# PCB-ENCODER4N.net
KiCad netlist of a schematic drawn in EAGLE
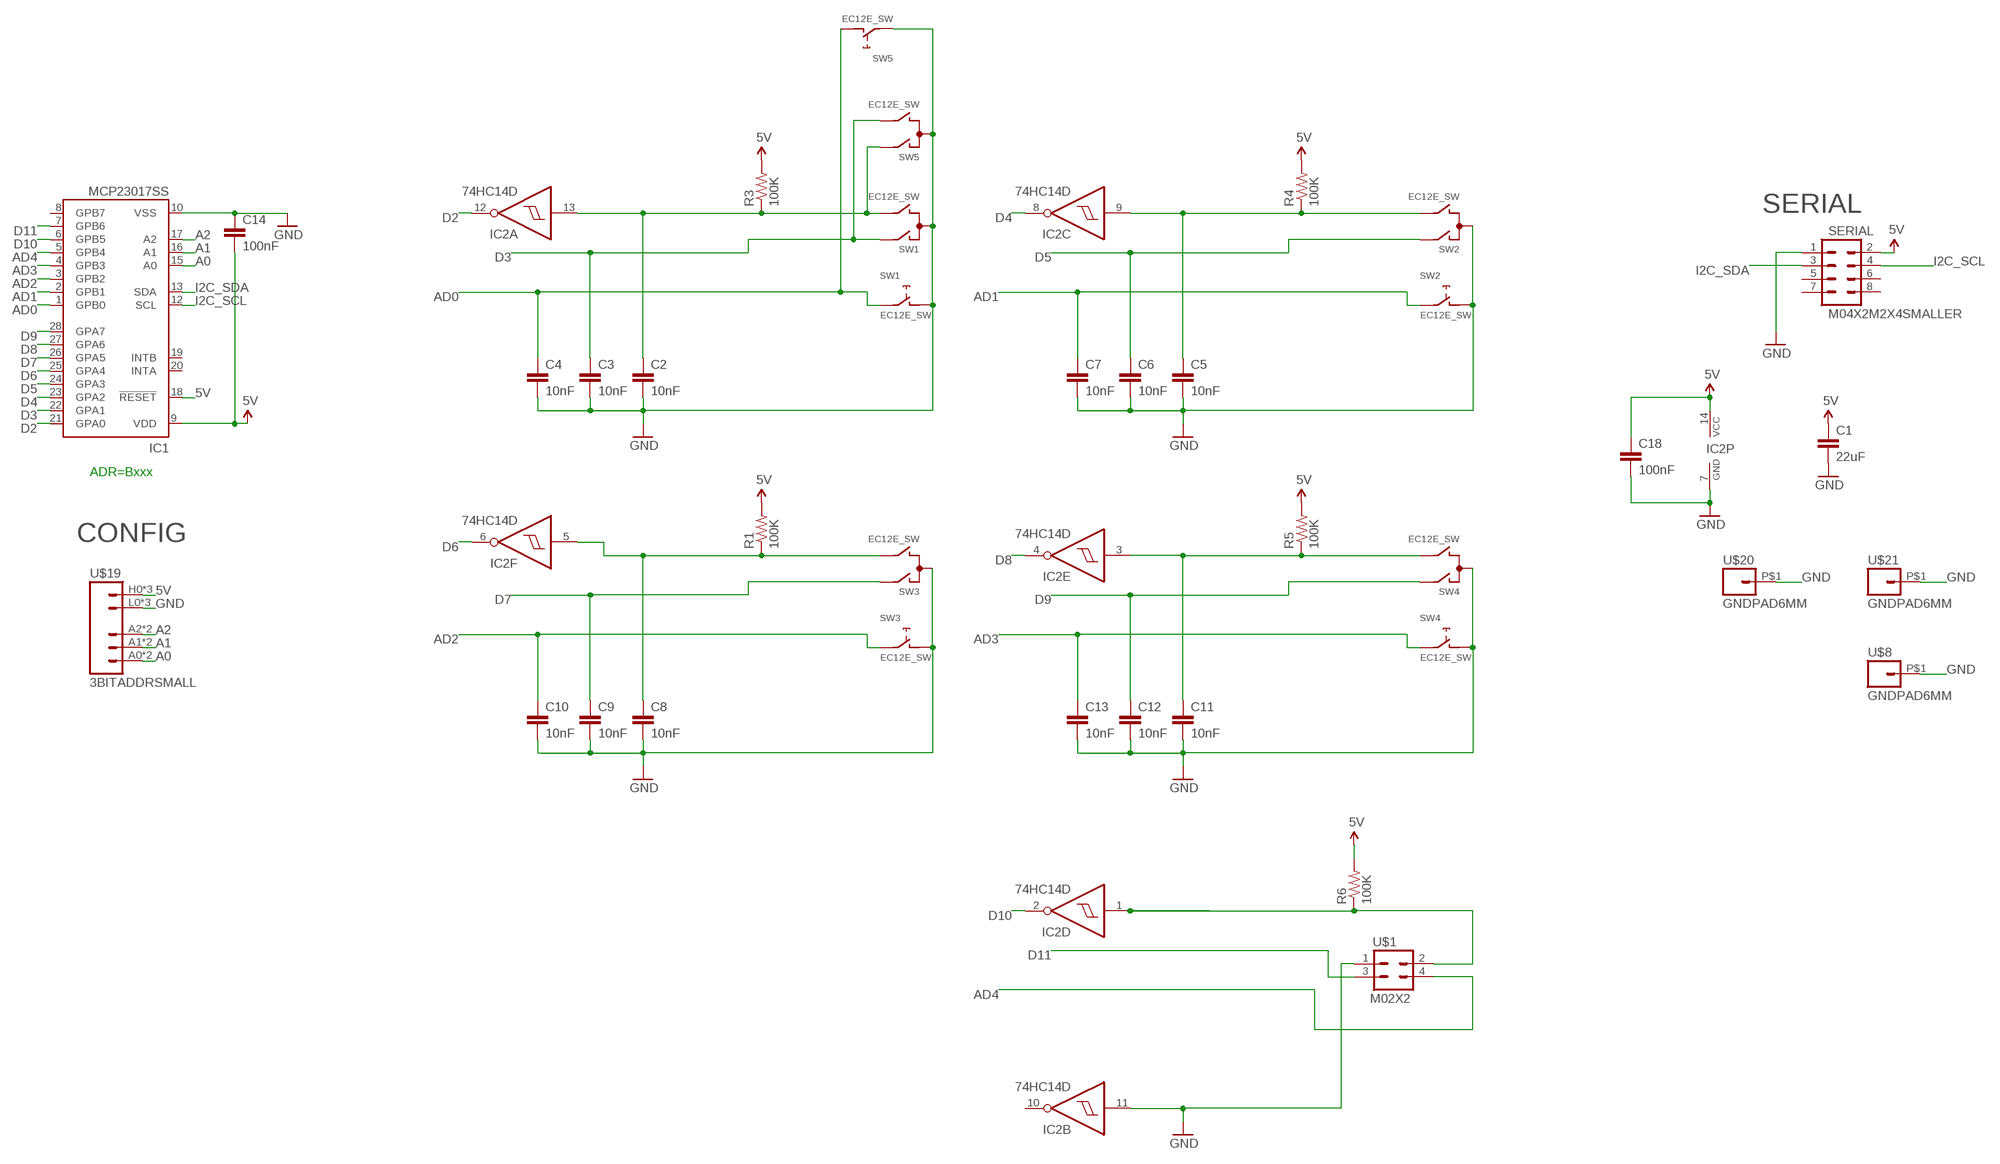
[diagram p0: schematic, sheet 1]

(export (version "E")
  (design (tool "Eeschema 10.0.6"))
  (components
    (comp (ref "C1")
      (value "22uF")
      (footprint "eagle-import:0805")
      (libsource (lib "eagle-import") (part "CAP0805"))
    )
    (comp (ref "C2")
      (value "10nF")
      (footprint "eagle-import:0603-CAP")
      (libsource (lib "eagle-import") (part "CAP0603-CAP"))
    )
    (comp (ref "C3")
      (value "10nF")
      (footprint "eagle-import:0603-CAP")
      (libsource (lib "eagle-import") (part "CAP0603-CAP"))
    )
    (comp (ref "C4")
      (value "10nF")
      (footprint "eagle-import:0603-CAP")
      (libsource (lib "eagle-import") (part "CAP0603-CAP"))
    )
    (comp (ref "C5")
      (value "10nF")
      (footprint "eagle-import:0603-CAP")
      (libsource (lib "eagle-import") (part "CAP0603-CAP"))
    )
    (comp (ref "C6")
      (value "10nF")
      (footprint "eagle-import:0603-CAP")
      (libsource (lib "eagle-import") (part "CAP0603-CAP"))
    )
    (comp (ref "C7")
      (value "10nF")
      (footprint "eagle-import:0603-CAP")
      (libsource (lib "eagle-import") (part "CAP0603-CAP"))
    )
    (comp (ref "C8")
      (value "10nF")
      (footprint "eagle-import:0603-CAP")
      (libsource (lib "eagle-import") (part "CAP0603-CAP"))
    )
    (comp (ref "C9")
      (value "10nF")
      (footprint "eagle-import:0603-CAP")
      (libsource (lib "eagle-import") (part "CAP0603-CAP"))
    )
    (comp (ref "C10")
      (value "10nF")
      (footprint "eagle-import:0603-CAP")
      (libsource (lib "eagle-import") (part "CAP0603-CAP"))
    )
    (comp (ref "C11")
      (value "10nF")
      (footprint "eagle-import:0603-CAP")
      (libsource (lib "eagle-import") (part "CAP0603-CAP"))
    )
    (comp (ref "C12")
      (value "10nF")
      (footprint "eagle-import:0603-CAP")
      (libsource (lib "eagle-import") (part "CAP0603-CAP"))
    )
    (comp (ref "C13")
      (value "10nF")
      (footprint "eagle-import:0603-CAP")
      (libsource (lib "eagle-import") (part "CAP0603-CAP"))
    )
    (comp (ref "C14")
      (value "100nF")
      (footprint "eagle-import:0603-CAP")
      (libsource (lib "eagle-import") (part "CAP0603-CAP"))
    )
    (comp (ref "C18")
      (value "100nF")
      (footprint "eagle-import:0603-CAP")
      (libsource (lib "eagle-import") (part "CAP0603-CAP"))
    )
    (comp (ref "IC1")
      (value "MCP23017SS")
      (footprint "eagle-import:SSOP28")
      (fields
        (field (name "MF") "MICROCHIP")
        (field (name "MPN") "MCP23017-E/SS")
        (field (name "MPN_1") "MCP23017-E/SS")
        (field (name "OC_FARNELL") "1467674")
        (field (name "OC_NEWARK") "31K2960")
      )
      (libsource (lib "eagle-import") (part "MCP23017SS"))
    )
    (comp (ref "IC2")
      (value "74HC14D")
      (footprint "eagle-import:SO14")
      (libsource (lib "eagle-import") (part "7414DHC"))
    )
    (comp (ref "R1")
      (value "100K")
      (footprint "eagle-import:0603-RES")
      (libsource (lib "eagle-import") (part "RESISTOR0603-RES"))
    )
    (comp (ref "R3")
      (value "100K")
      (footprint "eagle-import:0603-RES")
      (libsource (lib "eagle-import") (part "RESISTOR0603-RES"))
    )
    (comp (ref "R4")
      (value "100K")
      (footprint "eagle-import:0603-RES")
      (libsource (lib "eagle-import") (part "RESISTOR0603-RES"))
    )
    (comp (ref "R5")
      (value "100K")
      (footprint "eagle-import:0603-RES")
      (libsource (lib "eagle-import") (part "RESISTOR0603-RES"))
    )
    (comp (ref "R6")
      (value "100K")
      (footprint "eagle-import:0603-RES")
      (libsource (lib "eagle-import") (part "RESISTOR0603-RES"))
    )
    (comp (ref "SERIAL")
      (value "M04X2M2X4SMALLER")
      (footprint "eagle-import:M2X4SMALLER")
      (libsource (lib "eagle-import") (part "M04X2M2X4SMALLER"))
    )
    (comp (ref "SW1")
      (value "EC12E_SW")
      (footprint "eagle-import:ALPS_EC12E_SW")
      (fields (field (name "MPN") "EC12E2424407"))
      (libsource (lib "eagle-import") (part "EC12E_SW"))
    )
    (comp (ref "SW2")
      (value "EC12E_SW")
      (footprint "eagle-import:ALPS_EC12E_SW")
      (fields (field (name "MPN") "EC12E2424407"))
      (libsource (lib "eagle-import") (part "EC12E_SW"))
    )
    (comp (ref "SW3")
      (value "EC12E_SW")
      (footprint "eagle-import:ALPS_EC12E_SW")
      (fields (field (name "MPN") "EC12E2424407"))
      (libsource (lib "eagle-import") (part "EC12E_SW"))
    )
    (comp (ref "SW4")
      (value "EC12E_SW")
      (footprint "eagle-import:ALPS_EC12E_SW")
      (fields (field (name "MPN") "EC12E2424407"))
      (libsource (lib "eagle-import") (part "EC12E_SW"))
    )
    (comp (ref "SW5")
      (value "EC12E_SW")
      (footprint "eagle-import:ALPS_EC12E_SW")
      (fields (field (name "MPN") "EC12E2424407"))
      (libsource (lib "eagle-import") (part "EC12E_SW"))
    )
    (comp (ref "U$1")
      (value "M02X2")
      (footprint "eagle-import:2X2")
      (libsource (lib "eagle-import") (part "M02X2"))
    )
    (comp (ref "U$8")
      (value "GNDPAD6MM")
      (footprint "eagle-import:3.2MMPAD6MM")
      (libsource (lib "eagle-import") (part "GNDPAD6MM"))
    )
    (comp (ref "U$19")
      (value "3BITADDRSMALL")
      (footprint "eagle-import:3BITADDR_SMALL")
      (libsource (lib "eagle-import") (part "3BITADDRSMALL"))
    )
    (comp (ref "U$20")
      (value "GNDPAD6MM")
      (footprint "eagle-import:3.2MMPAD6MM")
      (libsource (lib "eagle-import") (part "GNDPAD6MM"))
    )
    (comp (ref "U$21")
      (value "GNDPAD6MM")
      (footprint "eagle-import:3.2MMPAD6MM")
      (libsource (lib "eagle-import") (part "GNDPAD6MM"))
    )
  )
  (nets
    (net (code "1") (name "/A0") (class "Default")
      (node (ref "IC1") (pin "15") (pinfunction "A0_15") (pintype "input"))
      (node (ref "U$19") (pin "A0") (pinfunction "A0_A0") (pintype "passive"))
      (node (ref "U$19") (pin "AS0") (pinfunction "A0_AS0") (pintype "passive"))
    )
    (net (code "2") (name "/A1") (class "Default")
      (node (ref "IC1") (pin "16") (pinfunction "A1_16") (pintype "input"))
      (node (ref "U$19") (pin "A1") (pinfunction "A1_A1") (pintype "passive"))
      (node (ref "U$19") (pin "AS1") (pinfunction "A1_AS1") (pintype "passive"))
    )
    (net (code "3") (name "/A2") (class "Default")
      (node (ref "IC1") (pin "17") (pinfunction "A2_17") (pintype "input"))
      (node (ref "U$19") (pin "A2") (pinfunction "A2_A2") (pintype "passive"))
      (node (ref "U$19") (pin "AS2") (pinfunction "A2_AS2") (pintype "passive"))
    )
    (net (code "4") (name "/AD0") (class "Default")
      (node (ref "C4") (pin "1") (pinfunction "1_1") (pintype "passive"))
      (node (ref "IC1") (pin "1") (pinfunction "GPB0_1") (pintype "bidirectional"))
      (node (ref "SW1") (pin "E") (pinfunction "2_E") (pintype "passive"))
      (node (ref "SW5") (pin "D") (pinfunction "1_D") (pintype "passive"))
    )
    (net (code "5") (name "/AD1") (class "Default")
      (node (ref "C7") (pin "1") (pinfunction "1_1") (pintype "passive"))
      (node (ref "IC1") (pin "2") (pinfunction "GPB1_2") (pintype "bidirectional"))
      (node (ref "SW2") (pin "E") (pinfunction "2_E") (pintype "passive"))
    )
    (net (code "6") (name "/AD2") (class "Default")
      (node (ref "C10") (pin "1") (pinfunction "1_1") (pintype "passive"))
      (node (ref "IC1") (pin "3") (pinfunction "GPB2_3") (pintype "bidirectional"))
      (node (ref "SW3") (pin "E") (pinfunction "2_E") (pintype "passive"))
    )
    (net (code "7") (name "/AD3") (class "Default")
      (node (ref "C13") (pin "1") (pinfunction "1_1") (pintype "passive"))
      (node (ref "IC1") (pin "4") (pinfunction "GPB3_4") (pintype "bidirectional"))
      (node (ref "SW4") (pin "E") (pinfunction "2_E") (pintype "passive"))
    )
    (net (code "8") (name "/AD4") (class "Default")
      (node (ref "IC1") (pin "5") (pinfunction "GPB4_5") (pintype "bidirectional"))
      (node (ref "U$1") (pin "4") (pinfunction "4_4") (pintype "passive"))
    )
    (net (code "9") (name "/D2") (class "Default")
      (node (ref "IC1") (pin "21") (pinfunction "GPA0_21") (pintype "bidirectional"))
      (node (ref "IC2") (pin "12") (pinfunction "O_12") (pintype "output"))
    )
    (net (code "10") (name "/D3") (class "Default")
      (node (ref "C3") (pin "1") (pinfunction "1_1") (pintype "passive"))
      (node (ref "IC1") (pin "22") (pinfunction "GPA1_22") (pintype "bidirectional"))
      (node (ref "SW1") (pin "A") (pinfunction "A_A") (pintype "passive"))
      (node (ref "SW5") (pin "B") (pinfunction "B_B") (pintype "passive"))
    )
    (net (code "11") (name "/D4") (class "Default")
      (node (ref "IC1") (pin "23") (pinfunction "GPA2_23") (pintype "bidirectional"))
      (node (ref "IC2") (pin "8") (pinfunction "O_8") (pintype "output"))
    )
    (net (code "12") (name "/D5") (class "Default")
      (node (ref "C6") (pin "1") (pinfunction "1_1") (pintype "passive"))
      (node (ref "IC1") (pin "24") (pinfunction "GPA3_24") (pintype "bidirectional"))
      (node (ref "SW2") (pin "A") (pinfunction "A_A") (pintype "passive"))
    )
    (net (code "13") (name "/D6") (class "Default")
      (node (ref "IC1") (pin "25") (pinfunction "GPA4_25") (pintype "bidirectional"))
      (node (ref "IC2") (pin "6") (pinfunction "O_6") (pintype "output"))
    )
    (net (code "14") (name "/D7") (class "Default")
      (node (ref "C9") (pin "1") (pinfunction "1_1") (pintype "passive"))
      (node (ref "IC1") (pin "26") (pinfunction "GPA5_26") (pintype "bidirectional"))
      (node (ref "SW3") (pin "A") (pinfunction "A_A") (pintype "passive"))
    )
    (net (code "15") (name "/D8") (class "Default")
      (node (ref "IC1") (pin "27") (pinfunction "GPA6_27") (pintype "bidirectional"))
      (node (ref "IC2") (pin "4") (pinfunction "O_4") (pintype "output"))
    )
    (net (code "16") (name "/D9") (class "Default")
      (node (ref "C12") (pin "1") (pinfunction "1_1") (pintype "passive"))
      (node (ref "IC1") (pin "28") (pinfunction "GPA7_28") (pintype "bidirectional"))
      (node (ref "SW4") (pin "A") (pinfunction "A_A") (pintype "passive"))
    )
    (net (code "17") (name "/D10") (class "Default")
      (node (ref "IC1") (pin "6") (pinfunction "GPB5_6") (pintype "bidirectional"))
      (node (ref "IC2") (pin "2") (pinfunction "O_2") (pintype "output"))
    )
    (net (code "18") (name "/D11") (class "Default")
      (node (ref "IC1") (pin "7") (pinfunction "GPB6_7") (pintype "bidirectional"))
      (node (ref "U$1") (pin "3") (pinfunction "3_3") (pintype "passive"))
    )
    (net (code "19") (name "/I2C_SCL") (class "Default")
      (node (ref "IC1") (pin "12") (pinfunction "SCL_12") (pintype "input"))
      (node (ref "SERIAL") (pin "4") (pinfunction "4_4") (pintype "passive"))
    )
    (net (code "20") (name "/I2C_SDA") (class "Default")
      (node (ref "IC1") (pin "13") (pinfunction "SDA_13") (pintype "bidirectional"))
      (node (ref "SERIAL") (pin "3") (pinfunction "3_3") (pintype "passive"))
    )
    (net (code "21") (name "5V") (class "Default")
      (node (ref "C1") (pin "1") (pinfunction "1_1") (pintype "passive"))
      (node (ref "C14") (pin "2") (pinfunction "2_2") (pintype "passive"))
      (node (ref "C18") (pin "1") (pinfunction "1_1") (pintype "passive"))
      (node (ref "IC1") (pin "18") (pinfunction "~{RESET}_18") (pintype "input"))
      (node (ref "IC1") (pin "9") (pinfunction "VDD_9") (pintype "power_in"))
      (node (ref "IC2") (pin "14") (pinfunction "VCC_14") (pintype "power_in"))
      (node (ref "R1") (pin "2") (pinfunction "2_2") (pintype "passive"))
      (node (ref "R3") (pin "2") (pinfunction "2_2") (pintype "passive"))
      (node (ref "R4") (pin "2") (pinfunction "2_2") (pintype "passive"))
      (node (ref "R5") (pin "2") (pinfunction "2_2") (pintype "passive"))
      (node (ref "R6") (pin "2") (pinfunction "2_2") (pintype "passive"))
      (node (ref "SERIAL") (pin "2") (pinfunction "2_2") (pintype "passive"))
      (node (ref "U$19") (pin "H0") (pinfunction "VCC_H0") (pintype "passive"))
      (node (ref "U$19") (pin "H1") (pinfunction "VCC_H1") (pintype "passive"))
      (node (ref "U$19") (pin "H2") (pinfunction "VCC_H2") (pintype "passive"))
    )
    (net (code "22") (name "GND") (class "Default")
      (node (ref "C1") (pin "2") (pinfunction "2_2") (pintype "passive"))
      (node (ref "C10") (pin "2") (pinfunction "2_2") (pintype "passive"))
      (node (ref "C11") (pin "2") (pinfunction "2_2") (pintype "passive"))
      (node (ref "C12") (pin "2") (pinfunction "2_2") (pintype "passive"))
      (node (ref "C13") (pin "2") (pinfunction "2_2") (pintype "passive"))
      (node (ref "C14") (pin "1") (pinfunction "1_1") (pintype "passive"))
      (node (ref "C18") (pin "2") (pinfunction "2_2") (pintype "passive"))
      (node (ref "C2") (pin "2") (pinfunction "2_2") (pintype "passive"))
      (node (ref "C3") (pin "2") (pinfunction "2_2") (pintype "passive"))
      (node (ref "C4") (pin "2") (pinfunction "2_2") (pintype "passive"))
      (node (ref "C5") (pin "2") (pinfunction "2_2") (pintype "passive"))
      (node (ref "C6") (pin "2") (pinfunction "2_2") (pintype "passive"))
      (node (ref "C7") (pin "2") (pinfunction "2_2") (pintype "passive"))
      (node (ref "C8") (pin "2") (pinfunction "2_2") (pintype "passive"))
      (node (ref "C9") (pin "2") (pinfunction "2_2") (pintype "passive"))
      (node (ref "IC1") (pin "10") (pinfunction "VSS_10") (pintype "power_in"))
      (node (ref "IC2") (pin "11") (pinfunction "I_11") (pintype "input"))
      (node (ref "IC2") (pin "7") (pinfunction "GND_7") (pintype "power_in"))
      (node (ref "SERIAL") (pin "1") (pinfunction "1_1") (pintype "passive"))
      (node (ref "SW1") (pin "C") (pinfunction "C_C") (pintype "passive"))
      (node (ref "SW1") (pin "D") (pinfunction "1_D") (pintype "passive"))
      (node (ref "SW2") (pin "C") (pinfunction "C_C") (pintype "passive"))
      (node (ref "SW2") (pin "D") (pinfunction "1_D") (pintype "passive"))
      (node (ref "SW3") (pin "C") (pinfunction "C_C") (pintype "passive"))
      (node (ref "SW3") (pin "D") (pinfunction "1_D") (pintype "passive"))
      (node (ref "SW4") (pin "C") (pinfunction "C_C") (pintype "passive"))
      (node (ref "SW4") (pin "D") (pinfunction "1_D") (pintype "passive"))
      (node (ref "SW5") (pin "C") (pinfunction "C_C") (pintype "passive"))
      (node (ref "SW5") (pin "E") (pinfunction "2_E") (pintype "passive"))
      (node (ref "U$1") (pin "1") (pinfunction "1_1") (pintype "passive"))
      (node (ref "U$19") (pin "L0") (pinfunction "GND_L0") (pintype "passive"))
      (node (ref "U$19") (pin "L1") (pinfunction "GND_L1") (pintype "passive"))
      (node (ref "U$19") (pin "L2") (pinfunction "GND_L2") (pintype "passive"))
      (node (ref "U$20") (pin "P$1") (pinfunction "1_P$1") (pintype "passive"))
      (node (ref "U$21") (pin "P$1") (pinfunction "1_P$1") (pintype "passive"))
      (node (ref "U$8") (pin "P$1") (pinfunction "1_P$1") (pintype "passive"))
    )
    (net (code "23") (name "Net-(IC2A-I)") (class "Default")
      (node (ref "C2") (pin "1") (pinfunction "1_1") (pintype "passive"))
      (node (ref "IC2") (pin "13") (pinfunction "I_13") (pintype "input"))
      (node (ref "R3") (pin "1") (pinfunction "1_1") (pintype "passive"))
      (node (ref "SW1") (pin "B") (pinfunction "B_B") (pintype "passive"))
      (node (ref "SW5") (pin "A") (pinfunction "A_A") (pintype "passive"))
    )
    (net (code "24") (name "Net-(IC2C-I)") (class "Default")
      (node (ref "C5") (pin "1") (pinfunction "1_1") (pintype "passive"))
      (node (ref "IC2") (pin "9") (pinfunction "I_9") (pintype "input"))
      (node (ref "R4") (pin "1") (pinfunction "1_1") (pintype "passive"))
      (node (ref "SW2") (pin "B") (pinfunction "B_B") (pintype "passive"))
    )
    (net (code "25") (name "Net-(IC2D-I)") (class "Default")
      (node (ref "IC2") (pin "1") (pinfunction "I_1") (pintype "input"))
      (node (ref "R6") (pin "1") (pinfunction "1_1") (pintype "passive"))
      (node (ref "U$1") (pin "2") (pinfunction "2_2") (pintype "passive"))
    )
    (net (code "26") (name "Net-(IC2E-I)") (class "Default")
      (node (ref "C11") (pin "1") (pinfunction "1_1") (pintype "passive"))
      (node (ref "IC2") (pin "3") (pinfunction "I_3") (pintype "input"))
      (node (ref "R5") (pin "1") (pinfunction "1_1") (pintype "passive"))
      (node (ref "SW4") (pin "B") (pinfunction "B_B") (pintype "passive"))
    )
    (net (code "27") (name "Net-(IC2F-I)") (class "Default")
      (node (ref "C8") (pin "1") (pinfunction "1_1") (pintype "passive"))
      (node (ref "IC2") (pin "5") (pinfunction "I_5") (pintype "input"))
      (node (ref "R1") (pin "1") (pinfunction "1_1") (pintype "passive"))
      (node (ref "SW3") (pin "B") (pinfunction "B_B") (pintype "passive"))
    )
    (net (code "28") (name "unconnected-(IC1-GPB7-Pad8)") (class "Default")
      (node (ref "IC1") (pin "8") (pinfunction "GPB7_8") (pintype "bidirectional"))
    )
    (net (code "29") (name "unconnected-(IC1-INTA-Pad20)") (class "Default")
      (node (ref "IC1") (pin "20") (pinfunction "INTA_20") (pintype "output"))
    )
    (net (code "30") (name "unconnected-(IC1-INTB-Pad19)") (class "Default")
      (node (ref "IC1") (pin "19") (pinfunction "INTB_19") (pintype "output"))
    )
    (net (code "31") (name "unconnected-(IC2B-O-Pad10)") (class "Default")
      (node (ref "IC2") (pin "10") (pinfunction "O_10") (pintype "output"))
    )
    (net (code "32") (name "unconnected-(SERIAL-Pad5)") (class "Default")
      (node (ref "SERIAL") (pin "5") (pinfunction "5_5") (pintype "passive"))
    )
    (net (code "33") (name "unconnected-(SERIAL-Pad6)") (class "Default")
      (node (ref "SERIAL") (pin "6") (pinfunction "6_6") (pintype "passive"))
    )
    (net (code "34") (name "unconnected-(SERIAL-Pad7)") (class "Default")
      (node (ref "SERIAL") (pin "7") (pinfunction "7_7") (pintype "passive"))
    )
    (net (code "35") (name "unconnected-(SERIAL-Pad8)") (class "Default")
      (node (ref "SERIAL") (pin "8") (pinfunction "8_8") (pintype "passive"))
    )
  )
)
